# soundmeter.net
KiCad netlist of a schematic drawn in EAGLE
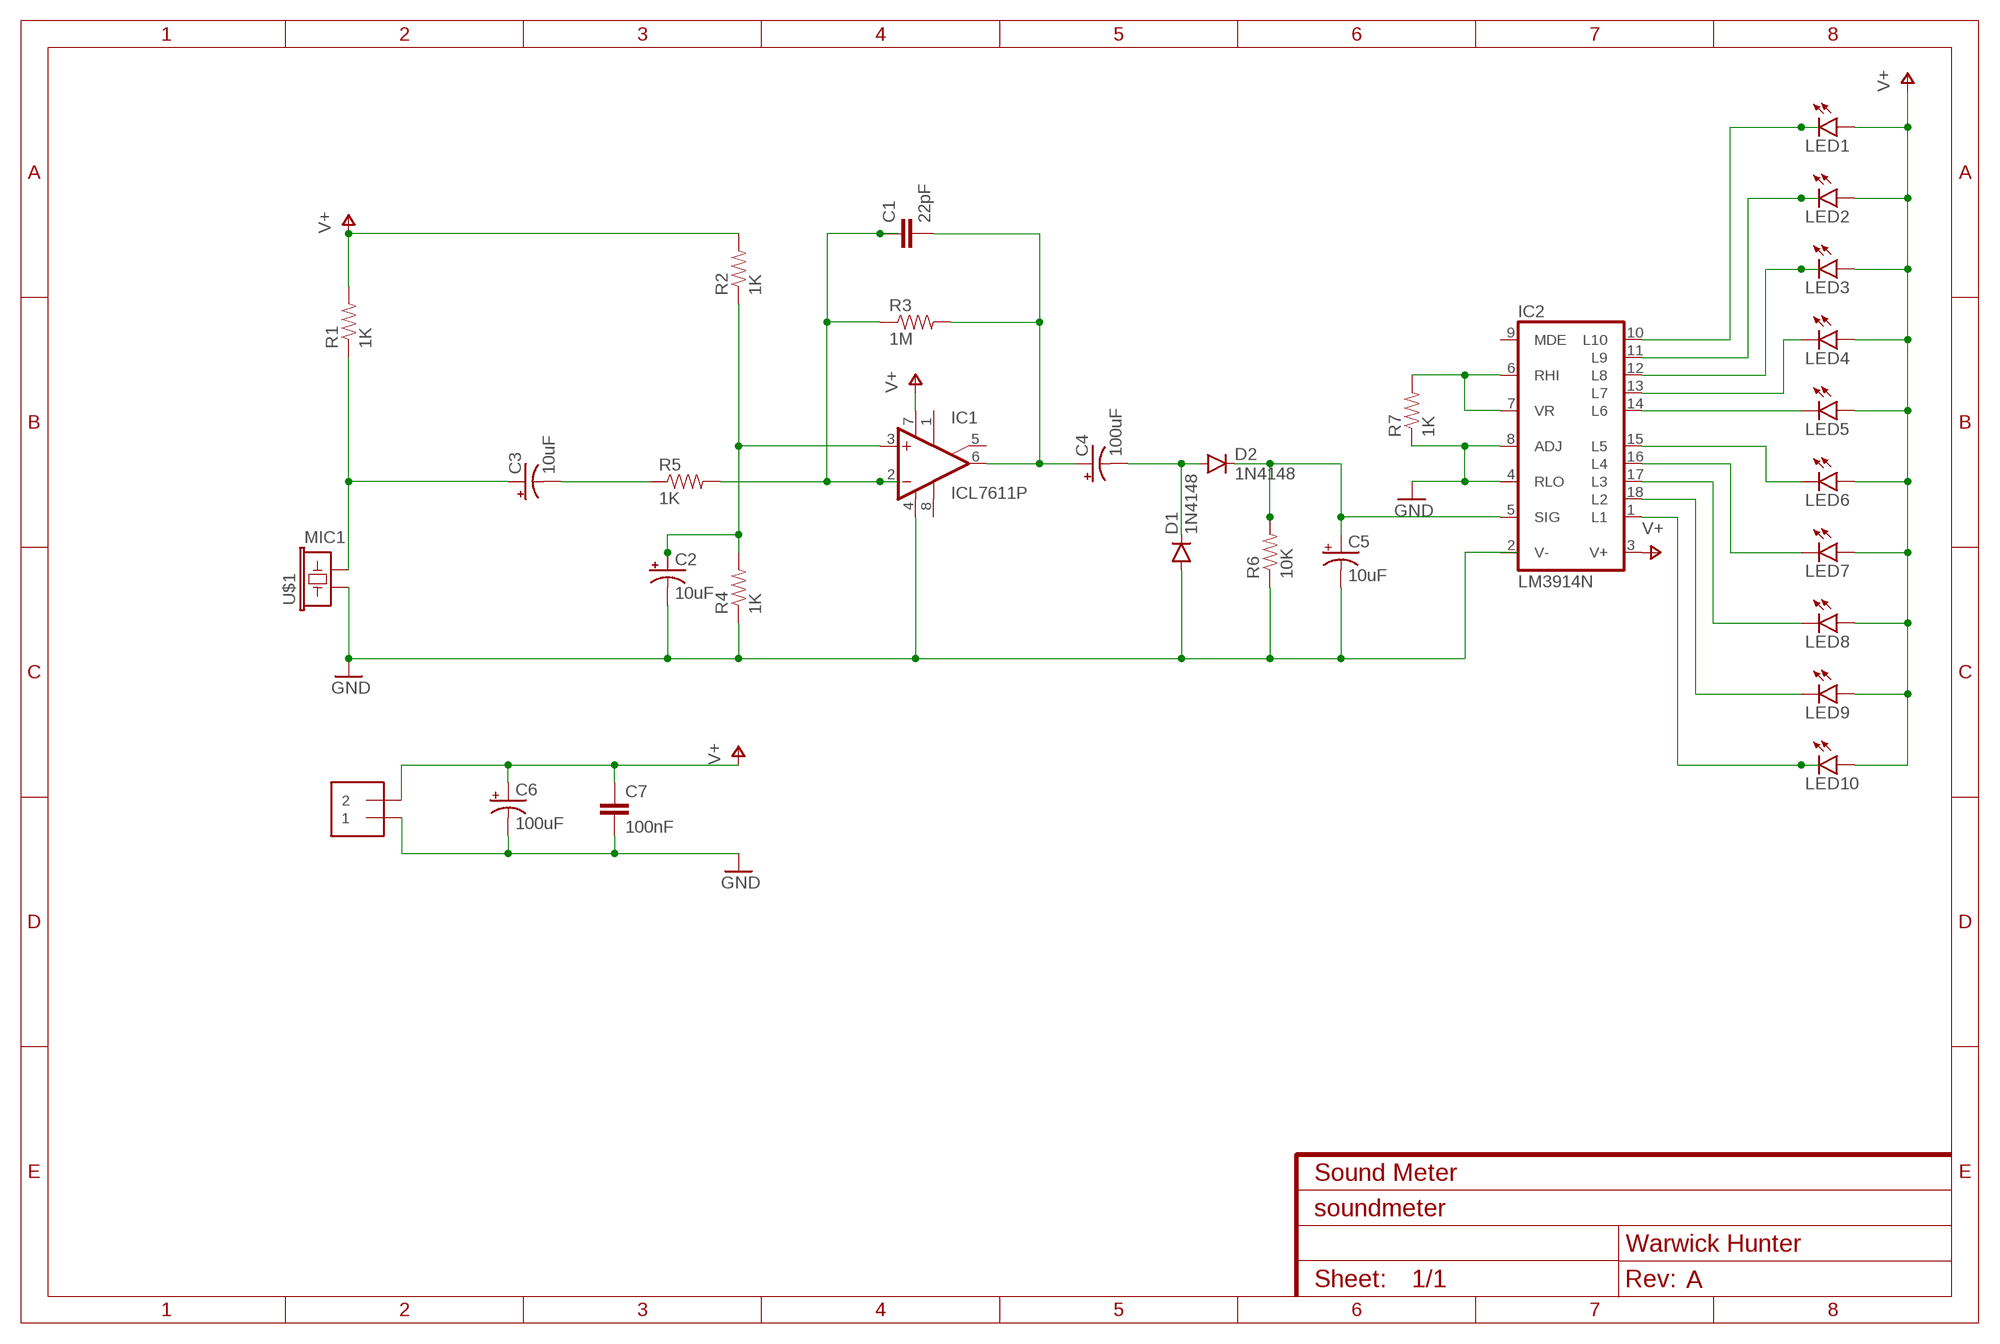
[diagram p0: schematic, sheet 1]

(export (version "E")
  (design (tool "Eeschema 10.0.6"))
  (components
    (comp (ref "C1")
      (value "22pF")
      (footprint "eagle-import:CAP-PTH-SMALL")
      (libsource (lib "eagle-import") (part "CAPPTH"))
    )
    (comp (ref "C2")
      (value "10uF")
      (footprint "eagle-import:CPOL-RADIAL-10UF-25V")
      (libsource (lib "eagle-import") (part "CAP_POLPTH2"))
    )
    (comp (ref "C3")
      (value "10uF")
      (footprint "eagle-import:CPOL-RADIAL-10UF-25V")
      (libsource (lib "eagle-import") (part "CAP_POLPTH2"))
    )
    (comp (ref "C4")
      (value "100uF")
      (footprint "eagle-import:CPOL-RADIAL-10UF-25V")
      (libsource (lib "eagle-import") (part "CAP_POLPTH2"))
    )
    (comp (ref "C5")
      (value "10uF")
      (footprint "eagle-import:CPOL-RADIAL-10UF-25V")
      (libsource (lib "eagle-import") (part "CAP_POLPTH2"))
    )
    (comp (ref "C6")
      (value "100uF")
      (footprint "eagle-import:CPOL-RADIAL-10UF-25V")
      (libsource (lib "eagle-import") (part "CAP_POLPTH2"))
    )
    (comp (ref "C7")
      (value "100nF")
      (footprint "eagle-import:CAP-PTH-SMALL")
      (libsource (lib "eagle-import") (part "CAPPTH"))
    )
    (comp (ref "D1")
      (value "1N4148")
      (footprint "eagle-import:DIODE-1N4148")
      (libsource (lib "eagle-import") (part "DIODE1N4148"))
    )
    (comp (ref "D2")
      (value "1N4148")
      (footprint "eagle-import:DIODE-1N4148")
      (libsource (lib "eagle-import") (part "DIODE1N4148"))
    )
    (comp (ref "IC1")
      (value "ICL7611P")
      (footprint "eagle-import:DIL08")
      (libsource (lib "eagle-import") (part "ICL7611P"))
    )
    (comp (ref "IC2")
      (value "LM3914N")
      (footprint "eagle-import:DIL18")
      (libsource (lib "eagle-import") (part "LM3914N"))
    )
    (comp (ref "J1")
      (value "1X2-3.5MM")
      (footprint "eagle-import:1X2-3.5MM")
      (libsource (lib "eagle-import") (part "1X2-3.5MM"))
    )
    (comp (ref "LED1")
      (value "LED3MM")
      (footprint "eagle-import:LED3MM")
      (libsource (lib "eagle-import") (part "LED3MM"))
    )
    (comp (ref "LED2")
      (value "LED3MM")
      (footprint "eagle-import:LED3MM")
      (libsource (lib "eagle-import") (part "LED3MM"))
    )
    (comp (ref "LED3")
      (value "LED3MM")
      (footprint "eagle-import:LED3MM")
      (libsource (lib "eagle-import") (part "LED3MM"))
    )
    (comp (ref "LED4")
      (value "LED3MM")
      (footprint "eagle-import:LED3MM")
      (libsource (lib "eagle-import") (part "LED3MM"))
    )
    (comp (ref "LED5")
      (value "LED3MM")
      (footprint "eagle-import:LED3MM")
      (libsource (lib "eagle-import") (part "LED3MM"))
    )
    (comp (ref "LED6")
      (value "LED3MM")
      (footprint "eagle-import:LED3MM")
      (libsource (lib "eagle-import") (part "LED3MM"))
    )
    (comp (ref "LED7")
      (value "LED3MM")
      (footprint "eagle-import:LED3MM")
      (libsource (lib "eagle-import") (part "LED3MM"))
    )
    (comp (ref "LED8")
      (value "LED3MM")
      (footprint "eagle-import:LED3MM")
      (libsource (lib "eagle-import") (part "LED3MM"))
    )
    (comp (ref "LED9")
      (value "LED3MM")
      (footprint "eagle-import:LED3MM")
      (libsource (lib "eagle-import") (part "LED3MM"))
    )
    (comp (ref "LED10")
      (value "LED3MM")
      (footprint "eagle-import:LED3MM")
      (libsource (lib "eagle-import") (part "LED3MM"))
    )
    (comp (ref "R1")
      (value "1K")
      (footprint "eagle-import:AXIAL-0.4")
      (libsource (lib "eagle-import") (part "RESISTORPTH-1/4W"))
    )
    (comp (ref "R2")
      (value "1K")
      (footprint "eagle-import:AXIAL-0.4")
      (libsource (lib "eagle-import") (part "RESISTORPTH-1/4W"))
    )
    (comp (ref "R3")
      (value "1M")
      (footprint "eagle-import:AXIAL-0.4")
      (libsource (lib "eagle-import") (part "RESISTORPTH-1/4W"))
    )
    (comp (ref "R4")
      (value "1K")
      (footprint "eagle-import:AXIAL-0.4")
      (libsource (lib "eagle-import") (part "RESISTORPTH-1/4W"))
    )
    (comp (ref "R5")
      (value "1K")
      (footprint "eagle-import:AXIAL-0.4")
      (libsource (lib "eagle-import") (part "RESISTORPTH-1/4W"))
    )
    (comp (ref "R6")
      (value "10K")
      (footprint "eagle-import:AXIAL-0.4")
      (libsource (lib "eagle-import") (part "RESISTORPTH-1/4W"))
    )
    (comp (ref "R7")
      (value "1K")
      (footprint "eagle-import:AXIAL-0.4")
      (libsource (lib "eagle-import") (part "RESISTORPTH-1/4W"))
    )
    (comp (ref "U$1")
      (value "MIC1")
      (footprint "eagle-import:MIC-9.7MM")
      (libsource (lib "eagle-import") (part "MIC9.7MM"))
    )
  )
  (nets
    (net (code "1") (name "/V-") (class "Default")
      (node (ref "IC2") (pin "2") (pinfunction "V-_2") (pintype "power_in"))
    )
    (net (code "2") (name "GND") (class "Default")
      (node (ref "C2") (pin "2") (pinfunction "-_2") (pintype "passive"))
      (node (ref "C5") (pin "2") (pinfunction "-_2") (pintype "passive"))
      (node (ref "C6") (pin "2") (pinfunction "-_2") (pintype "passive"))
      (node (ref "C7") (pin "2") (pinfunction "2_2") (pintype "passive"))
      (node (ref "D1") (pin "A") (pinfunction "A_A") (pintype "passive"))
      (node (ref "IC1") (pin "4") (pinfunction "V-_4") (pintype "power_in"))
      (node (ref "IC2") (pin "4") (pinfunction "RLO_4") (pintype "input"))
      (node (ref "IC2") (pin "8") (pinfunction "ADJ_8") (pintype "input"))
      (node (ref "J1") (pin "1") (pinfunction "1_1") (pintype "passive"))
      (node (ref "R4") (pin "P$1") (pinfunction "1_P$1") (pintype "passive"))
      (node (ref "R6") (pin "P$1") (pinfunction "1_P$1") (pintype "passive"))
      (node (ref "R7") (pin "P$1") (pinfunction "1_P$1") (pintype "passive"))
      (node (ref "U$1") (pin "1") (pinfunction "1_1") (pintype "passive"))
    )
    (net (code "3") (name "Net-(C2-+)") (class "Default")
      (node (ref "C2") (pin "1") (pinfunction "+_1") (pintype "passive"))
      (node (ref "IC1") (pin "3") (pinfunction "+IN_3") (pintype "input"))
      (node (ref "R2") (pin "P$1") (pinfunction "1_P$1") (pintype "passive"))
      (node (ref "R4") (pin "P$2") (pinfunction "2_P$2") (pintype "passive"))
    )
    (net (code "4") (name "Net-(C3-+)") (class "Default")
      (node (ref "C3") (pin "1") (pinfunction "+_1") (pintype "passive"))
      (node (ref "R1") (pin "P$1") (pinfunction "1_P$1") (pintype "passive"))
      (node (ref "U$1") (pin "2") (pinfunction "2_2") (pintype "passive"))
    )
    (net (code "5") (name "Net-(C3--)") (class "Default")
      (node (ref "C3") (pin "2") (pinfunction "-_2") (pintype "passive"))
      (node (ref "R5") (pin "P$1") (pinfunction "1_P$1") (pintype "passive"))
    )
    (net (code "6") (name "Net-(C4-+)") (class "Default")
      (node (ref "C1") (pin "2") (pinfunction "2_2") (pintype "passive"))
      (node (ref "C4") (pin "1") (pinfunction "+_1") (pintype "passive"))
      (node (ref "IC1") (pin "6") (pinfunction "OUT_6") (pintype "output"))
      (node (ref "R3") (pin "P$2") (pinfunction "2_P$2") (pintype "passive"))
    )
    (net (code "7") (name "Net-(C4--)") (class "Default")
      (node (ref "C4") (pin "2") (pinfunction "-_2") (pintype "passive"))
      (node (ref "D1") (pin "C") (pinfunction "C_C") (pintype "passive"))
      (node (ref "D2") (pin "A") (pinfunction "A_A") (pintype "passive"))
    )
    (net (code "8") (name "Net-(C5-+)") (class "Default")
      (node (ref "C5") (pin "1") (pinfunction "+_1") (pintype "passive"))
      (node (ref "D2") (pin "C") (pinfunction "C_C") (pintype "passive"))
      (node (ref "IC2") (pin "5") (pinfunction "SIG_5") (pintype "input"))
      (node (ref "R6") (pin "P$2") (pinfunction "2_P$2") (pintype "passive"))
    )
    (net (code "9") (name "Net-(IC1--IN)") (class "Default")
      (node (ref "C1") (pin "1") (pinfunction "1_1") (pintype "passive"))
      (node (ref "IC1") (pin "2") (pinfunction "-IN_2") (pintype "input"))
      (node (ref "R3") (pin "P$1") (pinfunction "1_P$1") (pintype "passive"))
      (node (ref "R5") (pin "P$2") (pinfunction "2_P$2") (pintype "passive"))
    )
    (net (code "10") (name "Net-(IC2-L1)") (class "Default")
      (node (ref "IC2") (pin "1") (pinfunction "L1_1") (pintype "output"))
      (node (ref "LED10") (pin "K") (pinfunction "C_K") (pintype "passive"))
    )
    (net (code "11") (name "Net-(IC2-L2)") (class "Default")
      (node (ref "IC2") (pin "18") (pinfunction "L2_18") (pintype "output"))
      (node (ref "LED9") (pin "K") (pinfunction "C_K") (pintype "passive"))
    )
    (net (code "12") (name "Net-(IC2-L3)") (class "Default")
      (node (ref "IC2") (pin "17") (pinfunction "L3_17") (pintype "output"))
      (node (ref "LED8") (pin "K") (pinfunction "C_K") (pintype "passive"))
    )
    (net (code "13") (name "Net-(IC2-L4)") (class "Default")
      (node (ref "IC2") (pin "16") (pinfunction "L4_16") (pintype "output"))
      (node (ref "LED7") (pin "K") (pinfunction "C_K") (pintype "passive"))
    )
    (net (code "14") (name "Net-(IC2-L5)") (class "Default")
      (node (ref "IC2") (pin "15") (pinfunction "L5_15") (pintype "output"))
      (node (ref "LED6") (pin "K") (pinfunction "C_K") (pintype "passive"))
    )
    (net (code "15") (name "Net-(IC2-L6)") (class "Default")
      (node (ref "IC2") (pin "14") (pinfunction "L6_14") (pintype "output"))
      (node (ref "LED5") (pin "K") (pinfunction "C_K") (pintype "passive"))
    )
    (net (code "16") (name "Net-(IC2-L7)") (class "Default")
      (node (ref "IC2") (pin "13") (pinfunction "L7_13") (pintype "output"))
      (node (ref "LED4") (pin "K") (pinfunction "C_K") (pintype "passive"))
    )
    (net (code "17") (name "Net-(IC2-L8)") (class "Default")
      (node (ref "IC2") (pin "12") (pinfunction "L8_12") (pintype "output"))
      (node (ref "LED3") (pin "K") (pinfunction "C_K") (pintype "passive"))
    )
    (net (code "18") (name "Net-(IC2-L9)") (class "Default")
      (node (ref "IC2") (pin "11") (pinfunction "L9_11") (pintype "output"))
      (node (ref "LED2") (pin "K") (pinfunction "C_K") (pintype "passive"))
    )
    (net (code "19") (name "Net-(IC2-L10)") (class "Default")
      (node (ref "IC2") (pin "10") (pinfunction "L10_10") (pintype "output"))
      (node (ref "LED1") (pin "K") (pinfunction "C_K") (pintype "passive"))
    )
    (net (code "20") (name "Net-(IC2-RHI)") (class "Default")
      (node (ref "IC2") (pin "6") (pinfunction "RHI_6") (pintype "input"))
      (node (ref "IC2") (pin "7") (pinfunction "VR_7") (pintype "output"))
      (node (ref "R7") (pin "P$2") (pinfunction "2_P$2") (pintype "passive"))
    )
    (net (code "21") (name "V+") (class "Default")
      (node (ref "C6") (pin "1") (pinfunction "+_1") (pintype "passive"))
      (node (ref "C7") (pin "1") (pinfunction "1_1") (pintype "passive"))
      (node (ref "IC1") (pin "7") (pinfunction "V+_7") (pintype "power_in"))
      (node (ref "IC2") (pin "3") (pinfunction "V+_3") (pintype "power_in"))
      (node (ref "J1") (pin "2") (pinfunction "2_2") (pintype "passive"))
      (node (ref "LED1") (pin "A") (pinfunction "A_A") (pintype "passive"))
      (node (ref "LED10") (pin "A") (pinfunction "A_A") (pintype "passive"))
      (node (ref "LED2") (pin "A") (pinfunction "A_A") (pintype "passive"))
      (node (ref "LED3") (pin "A") (pinfunction "A_A") (pintype "passive"))
      (node (ref "LED4") (pin "A") (pinfunction "A_A") (pintype "passive"))
      (node (ref "LED5") (pin "A") (pinfunction "A_A") (pintype "passive"))
      (node (ref "LED6") (pin "A") (pinfunction "A_A") (pintype "passive"))
      (node (ref "LED7") (pin "A") (pinfunction "A_A") (pintype "passive"))
      (node (ref "LED8") (pin "A") (pinfunction "A_A") (pintype "passive"))
      (node (ref "LED9") (pin "A") (pinfunction "A_A") (pintype "passive"))
      (node (ref "R1") (pin "P$2") (pinfunction "2_P$2") (pintype "passive"))
      (node (ref "R2") (pin "P$2") (pinfunction "2_P$2") (pintype "passive"))
    )
    (net (code "22") (name "unconnected-(IC1-ON1-Pad1)") (class "Default")
      (node (ref "IC1") (pin "1") (pinfunction "ON1_1") (pintype "passive"))
    )
    (net (code "23") (name "unconnected-(IC1-ON2-Pad5)") (class "Default")
      (node (ref "IC1") (pin "5") (pinfunction "ON2_5") (pintype "passive"))
    )
    (net (code "24") (name "unconnected-(IC1-OPT-Pad8)") (class "Default")
      (node (ref "IC1") (pin "8") (pinfunction "OPT_8") (pintype "passive"))
    )
    (net (code "25") (name "unconnected-(IC2-MDE-Pad9)") (class "Default")
      (node (ref "IC2") (pin "9") (pinfunction "MDE_9") (pintype "input"))
    )
  )
)
